# sx-signal84.net
KiCad netlist of a schematic drawn in EAGLE
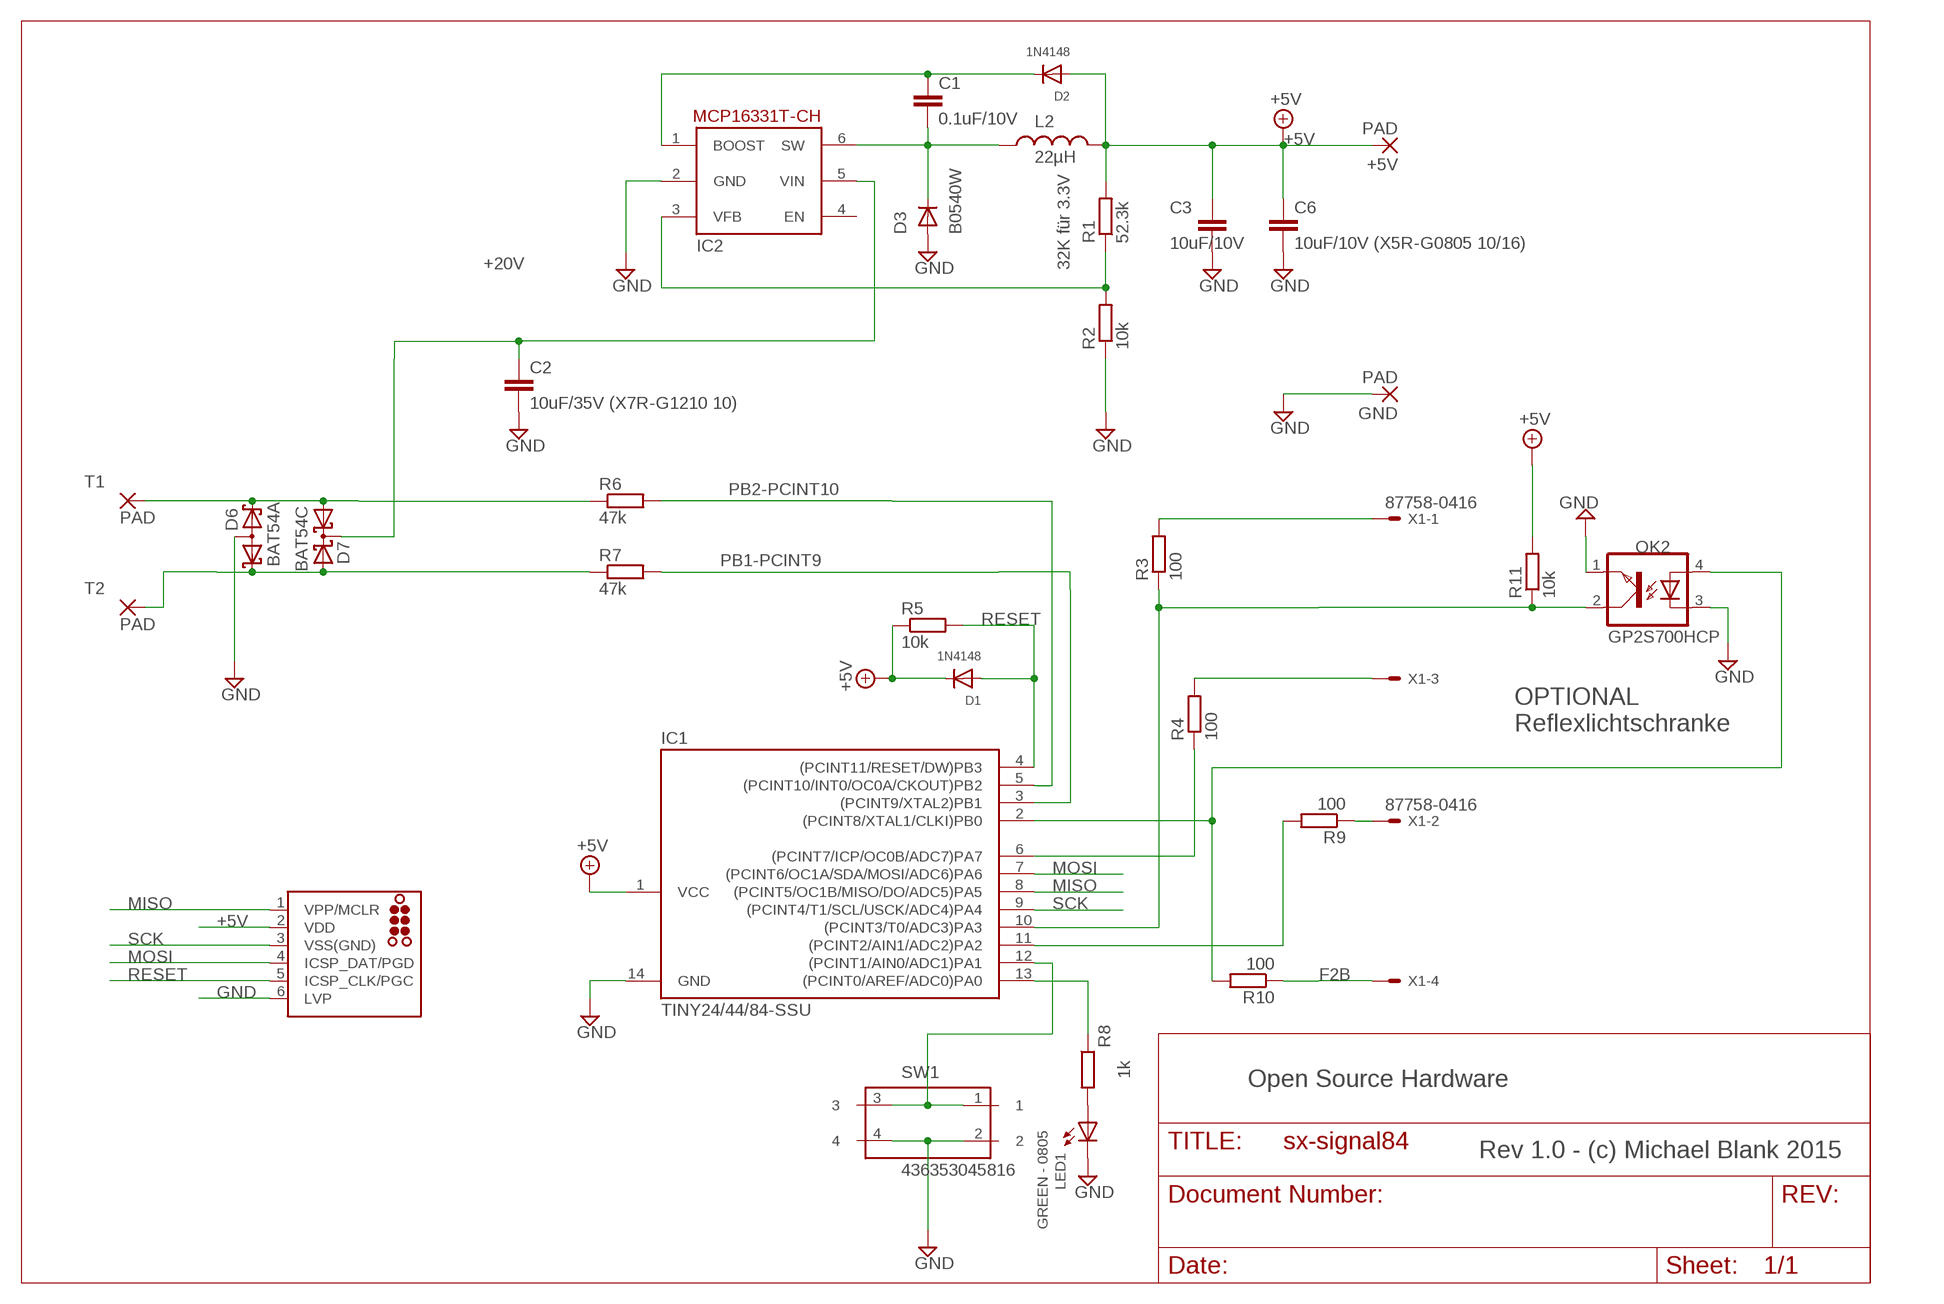
[diagram p0: schematic, sheet 1]

(export (version "E")
  (design (tool "Eeschema 10.0.6"))
  (components
    (comp (ref "+5V")
      (value "PAD")
      (footprint "eagle-import:SMD1,27-2,54")
      (libsource (lib "eagle-import") (part "SMD2"))
    )
    (comp (ref "C1")
      (value "0.1uF/10V")
      (footprint "eagle-import:C0805")
      (libsource (lib "eagle-import") (part "C-EUC0805"))
    )
    (comp (ref "C2")
      (value "10uF/35V (X7R-G1210 10)")
      (footprint "eagle-import:C1210")
      (libsource (lib "eagle-import") (part "C-EUC1210"))
    )
    (comp (ref "C3")
      (value "10uF/10V")
      (footprint "eagle-import:C0805")
      (libsource (lib "eagle-import") (part "C-EUC0805"))
    )
    (comp (ref "C6")
      (value "10uF/10V (X5R-G0805 10/16)")
      (footprint "eagle-import:C0805")
      (libsource (lib "eagle-import") (part "C-EUC0805"))
    )
    (comp (ref "D1")
      (value "1N4148")
      (footprint "eagle-import:SOD-323F")
      (libsource (lib "eagle-import") (part "DIODESOD-323F"))
    )
    (comp (ref "D2")
      (value "1N4148")
      (footprint "eagle-import:SOD-323F")
      (libsource (lib "eagle-import") (part "DIODESOD-323F"))
    )
    (comp (ref "D3")
      (value "B0540W")
      (footprint "eagle-import:SOD123")
      (libsource (lib "eagle-import") (part "DIODE-SOD123"))
    )
    (comp (ref "D6")
      (value "BAT54A")
      (footprint "eagle-import:SOT23")
      (libsource (lib "eagle-import") (part "BAT54A"))
    )
    (comp (ref "D7")
      (value "BAT54C")
      (footprint "eagle-import:SOT23")
      (libsource (lib "eagle-import") (part "BAT54C"))
    )
    (comp (ref "GND")
      (value "PAD")
      (footprint "eagle-import:SMD1,27-2,54")
      (libsource (lib "eagle-import") (part "SMD2"))
    )
    (comp (ref "IC1")
      (value "TINY24/44/84-SSU")
      (footprint "eagle-import:SOIC14")
      (libsource (lib "eagle-import") (part "TINY24/44/84-SSU"))
    )
    (comp (ref "IC2")
      (value "MCP16331")
      (footprint "eagle-import:SOT23-6")
      (libsource (lib "eagle-import") (part "MCP16331"))
    )
    (comp (ref "J1")
      (value "ISP")
      (footprint "eagle-import:TC2030-MCP-NL")
      (libsource (lib "eagle-import") (part "TC2030-MCP-NL"))
    )
    (comp (ref "L2")
      (value "22µH")
      (footprint "eagle-import:B82462G")
      (libsource (lib "eagle-import") (part "INDUCTOR-SPARKFUN-B82462G"))
    )
    (comp (ref "LED1")
      (value "GREEN - 0805")
      (footprint "eagle-import:LED-0805")
      (libsource (lib "eagle-import") (part "LED0805"))
    )
    (comp (ref "OK2")
      (value "GP2S700HCP")
      (footprint "eagle-import:SMD4-REFL")
      (libsource (lib "eagle-import") (part "GP2S700HCP"))
    )
    (comp (ref "R1")
      (value "52.3k")
      (footprint "eagle-import:R0805W")
      (libsource (lib "eagle-import") (part "R-EU_R0805W"))
    )
    (comp (ref "R2")
      (value "10k")
      (footprint "eagle-import:R0805W")
      (libsource (lib "eagle-import") (part "R-EU_R0805W"))
    )
    (comp (ref "R3")
      (value "100")
      (footprint "eagle-import:R0805W")
      (libsource (lib "eagle-import") (part "R-EU_R0805W"))
    )
    (comp (ref "R4")
      (value "100")
      (footprint "eagle-import:R0805W")
      (libsource (lib "eagle-import") (part "R-EU_R0805W"))
    )
    (comp (ref "R5")
      (value "10k")
      (footprint "eagle-import:R0805W")
      (libsource (lib "eagle-import") (part "R-EU_R0805W"))
    )
    (comp (ref "R6")
      (value "47k")
      (footprint "eagle-import:R0805W")
      (libsource (lib "eagle-import") (part "R-EU_R0805W"))
    )
    (comp (ref "R7")
      (value "47k")
      (footprint "eagle-import:R0805W")
      (libsource (lib "eagle-import") (part "R-EU_R0805W"))
    )
    (comp (ref "R8")
      (value "1k")
      (footprint "eagle-import:R0805W")
      (libsource (lib "eagle-import") (part "R-EU_R0805W"))
    )
    (comp (ref "R9")
      (value "100")
      (footprint "eagle-import:R0805W")
      (libsource (lib "eagle-import") (part "R-EU_R0805W"))
    )
    (comp (ref "R10")
      (value "100")
      (footprint "eagle-import:R0805W")
      (libsource (lib "eagle-import") (part "R-EU_R0805W"))
    )
    (comp (ref "R11")
      (value "10k")
      (footprint "eagle-import:R0805W")
      (libsource (lib "eagle-import") (part "R-EU_R0805W"))
    )
    (comp (ref "SW1")
      (value "436353045816")
      (footprint "eagle-import:436353045816")
      (libsource (lib "eagle-import") (part "436353045816"))
    )
    (comp (ref "T1")
      (value "PAD")
      (footprint "eagle-import:SMD1,27-2,54")
      (libsource (lib "eagle-import") (part "SMD2"))
    )
    (comp (ref "T2")
      (value "PAD")
      (footprint "eagle-import:SMD1,27-2,54")
      (libsource (lib "eagle-import") (part "SMD2"))
    )
    (comp (ref "X1")
      (value "87758-0416")
      (footprint "eagle-import:87758-0416")
      (fields (field (name "MF") "FARNELL"))
      (libsource (lib "eagle-import") (part "87758-0416"))
    )
  )
  (nets
    (net (code "1") (name "+5V") (class "Default")
      (node (ref "+5V") (pin "1") (pinfunction "P_1") (pintype "passive"))
      (node (ref "C3") (pin "1") (pinfunction "1_1") (pintype "passive"))
      (node (ref "C6") (pin "1") (pinfunction "1_1") (pintype "passive"))
      (node (ref "D1") (pin "C") (pinfunction "C_C") (pintype "passive"))
      (node (ref "D2") (pin "A") (pinfunction "A_A") (pintype "passive"))
      (node (ref "IC1") (pin "1") (pinfunction "VCC_1") (pintype "power_in"))
      (node (ref "J1") (pin "2") (pinfunction "VDD_2") (pintype "power_in"))
      (node (ref "L2") (pin "P$2") (pinfunction "2_P$2") (pintype "passive"))
      (node (ref "R1") (pin "2") (pinfunction "2_2") (pintype "passive"))
      (node (ref "R11") (pin "2") (pinfunction "2_2") (pintype "passive"))
      (node (ref "R5") (pin "1") (pinfunction "1_1") (pintype "passive"))
    )
    (net (code "2") (name "/+20V") (class "Default")
      (node (ref "C2") (pin "1") (pinfunction "1_1") (pintype "passive"))
      (node (ref "D7") (pin "3") (pinfunction "CC_3") (pintype "passive"))
      (node (ref "IC2") (pin "5") (pinfunction "VIN_5") (pintype "power_in"))
    )
    (net (code "3") (name "/F2B") (class "Default")
      (node (ref "R10") (pin "1") (pinfunction "1_1") (pintype "passive"))
      (node (ref "X1") (pin "4") (pinfunction "S_4") (pintype "passive"))
    )
    (net (code "4") (name "/MISO") (class "Default")
      (node (ref "IC1") (pin "8") (pinfunction "(PCINT5/OC1B/MISO/DO/ADC5)PA5_8") (pintype "bidirectional"))
      (node (ref "J1") (pin "1") (pinfunction "VPP/MCLR_1") (pintype "passive"))
    )
    (net (code "5") (name "/MOSI") (class "Default")
      (node (ref "IC1") (pin "7") (pinfunction "(PCINT6/OC1A/SDA/MOSI/ADC6)PA6_7") (pintype "bidirectional"))
      (node (ref "J1") (pin "4") (pinfunction "ICSP_DAT/PGD_4") (pintype "bidirectional"))
    )
    (net (code "6") (name "/PB1-PCINT9") (class "Default")
      (node (ref "IC1") (pin "3") (pinfunction "(PCINT9/XTAL2)PB1_3") (pintype "bidirectional"))
      (node (ref "R7") (pin "2") (pinfunction "2_2") (pintype "passive"))
    )
    (net (code "7") (name "/PB2-PCINT10") (class "Default")
      (node (ref "IC1") (pin "5") (pinfunction "(PCINT10/INT0/OC0A/CKOUT)PB2_5") (pintype "bidirectional"))
      (node (ref "R6") (pin "2") (pinfunction "2_2") (pintype "passive"))
    )
    (net (code "8") (name "/RESET") (class "Default")
      (node (ref "D1") (pin "A") (pinfunction "A_A") (pintype "passive"))
      (node (ref "IC1") (pin "4") (pinfunction "(PCINT11/RESET/DW)PB3_4") (pintype "bidirectional"))
      (node (ref "J1") (pin "5") (pinfunction "ICSP_CLK/PGC_5") (pintype "output"))
      (node (ref "R5") (pin "2") (pinfunction "2_2") (pintype "passive"))
    )
    (net (code "9") (name "/SCK") (class "Default")
      (node (ref "IC1") (pin "9") (pinfunction "(PCINT4/T1/SCL/USCK/ADC4)PA4_9") (pintype "bidirectional"))
      (node (ref "J1") (pin "3") (pinfunction "VSS(GND)_3") (pintype "power_in"))
    )
    (net (code "10") (name "GND") (class "Default")
      (node (ref "C2") (pin "2") (pinfunction "2_2") (pintype "passive"))
      (node (ref "C3") (pin "2") (pinfunction "2_2") (pintype "passive"))
      (node (ref "C6") (pin "2") (pinfunction "2_2") (pintype "passive"))
      (node (ref "D3") (pin "A") (pinfunction "A_A") (pintype "passive"))
      (node (ref "D6") (pin "3") (pinfunction "AA_3") (pintype "passive"))
      (node (ref "GND") (pin "1") (pinfunction "P_1") (pintype "passive"))
      (node (ref "IC1") (pin "14") (pinfunction "GND_14") (pintype "power_in"))
      (node (ref "IC2") (pin "2") (pinfunction "GND_2") (pintype "power_in"))
      (node (ref "J1") (pin "6") (pinfunction "LVP_6") (pintype "bidirectional"))
      (node (ref "LED1") (pin "C") (pinfunction "C_C") (pintype "passive"))
      (node (ref "OK2") (pin "1") (pinfunction "EMIT_1") (pintype "passive"))
      (node (ref "OK2") (pin "3") (pinfunction "C_3") (pintype "passive"))
      (node (ref "R2") (pin "1") (pinfunction "1_1") (pintype "passive"))
      (node (ref "SW1") (pin "2") (pinfunction "2_2") (pintype "bidirectional"))
      (node (ref "SW1") (pin "4") (pinfunction "4_4") (pintype "bidirectional"))
    )
    (net (code "11") (name "Net-(D6-K1)") (class "Default")
      (node (ref "D6") (pin "1") (pinfunction "K1_1") (pintype "passive"))
      (node (ref "D7") (pin "2") (pinfunction "A2_2") (pintype "passive"))
      (node (ref "R7") (pin "1") (pinfunction "1_1") (pintype "passive"))
      (node (ref "T2") (pin "1") (pinfunction "P_1") (pintype "passive"))
    )
    (net (code "12") (name "Net-(D6-K2)") (class "Default")
      (node (ref "D6") (pin "2") (pinfunction "K2_2") (pintype "passive"))
      (node (ref "D7") (pin "1") (pinfunction "A1_1") (pintype "passive"))
      (node (ref "R6") (pin "1") (pinfunction "1_1") (pintype "passive"))
      (node (ref "T1") (pin "1") (pinfunction "P_1") (pintype "passive"))
    )
    (net (code "13") (name "Net-(IC1-(PCINT0{slash}AREF{slash}ADC0)PA0)") (class "Default")
      (node (ref "IC1") (pin "13") (pinfunction "(PCINT0/AREF/ADC0)PA0_13") (pintype "bidirectional"))
      (node (ref "R8") (pin "1") (pinfunction "1_1") (pintype "passive"))
    )
    (net (code "14") (name "Net-(IC1-(PCINT1{slash}AIN0{slash}ADC1)PA1)") (class "Default")
      (node (ref "IC1") (pin "12") (pinfunction "(PCINT1/AIN0/ADC1)PA1_12") (pintype "bidirectional"))
      (node (ref "SW1") (pin "1") (pinfunction "1_1") (pintype "bidirectional"))
      (node (ref "SW1") (pin "3") (pinfunction "3_3") (pintype "bidirectional"))
    )
    (net (code "15") (name "Net-(IC1-(PCINT2{slash}AIN1{slash}ADC2)PA2)") (class "Default")
      (node (ref "IC1") (pin "11") (pinfunction "(PCINT2/AIN1/ADC2)PA2_11") (pintype "bidirectional"))
      (node (ref "R9") (pin "2") (pinfunction "2_2") (pintype "passive"))
    )
    (net (code "16") (name "Net-(IC1-(PCINT3{slash}T0{slash}ADC3)PA3)") (class "Default")
      (node (ref "IC1") (pin "10") (pinfunction "(PCINT3/T0/ADC3)PA3_10") (pintype "bidirectional"))
      (node (ref "OK2") (pin "2") (pinfunction "COL_2") (pintype "passive"))
      (node (ref "R11") (pin "1") (pinfunction "1_1") (pintype "passive"))
      (node (ref "R3") (pin "1") (pinfunction "1_1") (pintype "passive"))
    )
    (net (code "17") (name "Net-(IC1-(PCINT7{slash}ICP{slash}OC0B{slash}ADC7)PA7)") (class "Default")
      (node (ref "IC1") (pin "6") (pinfunction "(PCINT7/ICP/OC0B/ADC7)PA7_6") (pintype "bidirectional"))
      (node (ref "R4") (pin "1") (pinfunction "1_1") (pintype "passive"))
    )
    (net (code "18") (name "Net-(IC1-(PCINT8{slash}XTAL1{slash}CLKI)PB0)") (class "Default")
      (node (ref "IC1") (pin "2") (pinfunction "(PCINT8/XTAL1/CLKI)PB0_2") (pintype "bidirectional"))
      (node (ref "OK2") (pin "4") (pinfunction "A_4") (pintype "passive"))
      (node (ref "R10") (pin "2") (pinfunction "2_2") (pintype "passive"))
    )
    (net (code "19") (name "Net-(IC2-BOOST)") (class "Default")
      (node (ref "C1") (pin "1") (pinfunction "1_1") (pintype "passive"))
      (node (ref "D2") (pin "C") (pinfunction "C_C") (pintype "passive"))
      (node (ref "IC2") (pin "1") (pinfunction "BOOST_1") (pintype "input"))
    )
    (net (code "20") (name "Net-(IC2-SW)") (class "Default")
      (node (ref "C1") (pin "2") (pinfunction "2_2") (pintype "passive"))
      (node (ref "D3") (pin "C") (pinfunction "C_C") (pintype "passive"))
      (node (ref "IC2") (pin "6") (pinfunction "SW_6") (pintype "output"))
      (node (ref "L2") (pin "P$1") (pinfunction "1_P$1") (pintype "passive"))
    )
    (net (code "21") (name "Net-(IC2-VFB)") (class "Default")
      (node (ref "IC2") (pin "3") (pinfunction "VFB_3") (pintype "bidirectional"))
      (node (ref "R1") (pin "1") (pinfunction "1_1") (pintype "passive"))
      (node (ref "R2") (pin "2") (pinfunction "2_2") (pintype "passive"))
    )
    (net (code "22") (name "Net-(LED1-PadA)") (class "Default")
      (node (ref "LED1") (pin "A") (pinfunction "A_A") (pintype "passive"))
      (node (ref "R8") (pin "2") (pinfunction "2_2") (pintype "passive"))
    )
    (net (code "23") (name "Net-(X1A-S)") (class "Default")
      (node (ref "R3") (pin "2") (pinfunction "2_2") (pintype "passive"))
      (node (ref "X1") (pin "1") (pinfunction "S_1") (pintype "passive"))
    )
    (net (code "24") (name "Net-(X1B-S)") (class "Default")
      (node (ref "R9") (pin "1") (pinfunction "1_1") (pintype "passive"))
      (node (ref "X1") (pin "2") (pinfunction "S_2") (pintype "passive"))
    )
    (net (code "25") (name "Net-(X1C-S)") (class "Default")
      (node (ref "R4") (pin "2") (pinfunction "2_2") (pintype "passive"))
      (node (ref "X1") (pin "3") (pinfunction "S_3") (pintype "passive"))
    )
    (net (code "26") (name "unconnected-(IC2-EN-Pad4)") (class "Default")
      (node (ref "IC2") (pin "4") (pinfunction "EN_4") (pintype "input"))
    )
  )
)
